# BOOST_LM5112.net
KiCad netlist of a schematic drawn in Altium Designer
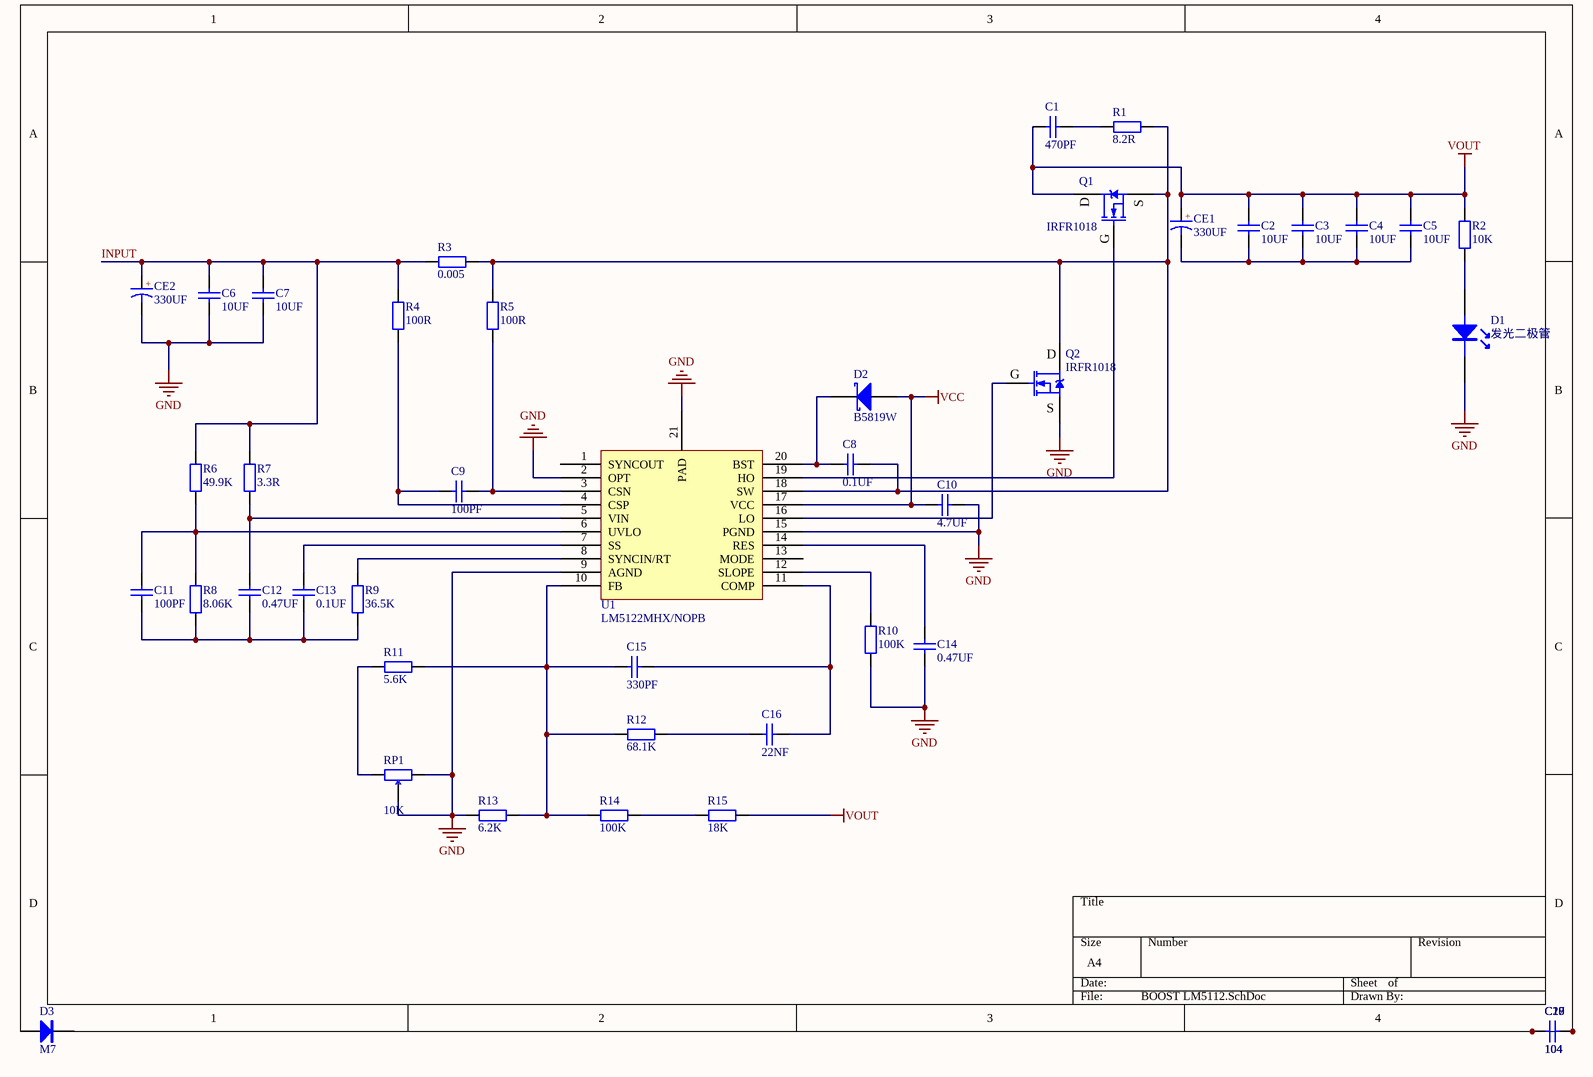
[diagram p0: BOOST LM5112.SchDoc]

(export (version "E")
  (design (tool "Eeschema 10.0.6"))
  (components
    (comp (ref "C1")
      (value "470PF")
      (footprint "C-10uF")
      (description "瓷片电容")
      (libsource (lib "0.1 - 电阻-电容-电感-磁珠-电位器") (part "CC"))
    )
    (comp (ref "C2")
      (value "10UF")
      (footprint "C-10uF")
      (description "瓷片电容")
      (libsource (lib "0.1 - 电阻-电容-电感-磁珠-电位器") (part "CC"))
    )
    (comp (ref "C3")
      (value "10UF")
      (footprint "C-10uF")
      (description "瓷片电容")
      (libsource (lib "0.1 - 电阻-电容-电感-磁珠-电位器") (part "CC"))
    )
    (comp (ref "C4")
      (value "10UF")
      (footprint "C-10uF")
      (description "瓷片电容")
      (libsource (lib "0.1 - 电阻-电容-电感-磁珠-电位器") (part "CC"))
    )
    (comp (ref "C5")
      (value "10UF")
      (footprint "C-10uF")
      (description "瓷片电容")
      (libsource (lib "0.1 - 电阻-电容-电感-磁珠-电位器") (part "CC"))
    )
    (comp (ref "C6")
      (value "10UF")
      (footprint "C-10uF")
      (description "瓷片电容")
      (libsource (lib "0.1 - 电阻-电容-电感-磁珠-电位器") (part "CC"))
    )
    (comp (ref "C7")
      (value "10UF")
      (footprint "C-10uF")
      (description "瓷片电容")
      (libsource (lib "0.1 - 电阻-电容-电感-磁珠-电位器") (part "CC"))
    )
    (comp (ref "C8")
      (value "0.1UF")
      (description "瓷片电容")
      (libsource (lib "0.1 - 电阻-电容-电感-磁珠-电位器") (part "CC"))
    )
    (comp (ref "C9")
      (value "100PF")
      (footprint "C-10uF")
      (description "瓷片电容")
      (libsource (lib "0.1 - 电阻-电容-电感-磁珠-电位器") (part "CC"))
    )
    (comp (ref "C10")
      (value "4.7UF")
      (footprint "C-10uF")
      (description "瓷片电容")
      (libsource (lib "0.1 - 电阻-电容-电感-磁珠-电位器") (part "CC"))
    )
    (comp (ref "C11")
      (value "100PF")
      (footprint "C-10uF")
      (description "瓷片电容")
      (libsource (lib "0.1 - 电阻-电容-电感-磁珠-电位器") (part "CC"))
    )
    (comp (ref "C12")
      (value "0.47UF")
      (footprint "C-10uF")
      (description "瓷片电容")
      (libsource (lib "0.1 - 电阻-电容-电感-磁珠-电位器") (part "CC"))
    )
    (comp (ref "C13")
      (value "0.1UF")
      (footprint "C-10uF")
      (description "瓷片电容")
      (libsource (lib "0.1 - 电阻-电容-电感-磁珠-电位器") (part "CC"))
    )
    (comp (ref "C14")
      (value "0.47UF")
      (footprint "C-10uF")
      (description "瓷片电容")
      (libsource (lib "0.1 - 电阻-电容-电感-磁珠-电位器") (part "CC"))
    )
    (comp (ref "C15")
      (value "330PF")
      (footprint "C-10uF")
      (description "瓷片电容")
      (libsource (lib "0.1 - 电阻-电容-电感-磁珠-电位器") (part "CC"))
    )
    (comp (ref "C16")
      (value "22NF")
      (footprint "C-10uF")
      (description "瓷片电容")
      (libsource (lib "0.1 - 电阻-电容-电感-磁珠-电位器") (part "CC"))
    )
    (comp (ref "C17")
      (value "104")
      (footprint "C-10uF")
      (description "瓷片电容")
      (libsource (lib "0.1 - 电阻-电容-电感-磁珠-电位器") (part "CC"))
    )
    (comp (ref "C18")
      (value "104")
      (footprint "C-10uF")
      (description "瓷片电容")
      (libsource (lib "0.1 - 电阻-电容-电感-磁珠-电位器") (part "CC"))
    )
    (comp (ref "C19")
      (value "104")
      (footprint "C-10uF")
      (description "瓷片电容")
      (libsource (lib "0.1 - 电阻-电容-电感-磁珠-电位器") (part "CC"))
    )
    (comp (ref "C20")
      (value "104")
      (footprint "C-10uF")
      (description "瓷片电容")
      (libsource (lib "0.1 - 电阻-电容-电感-磁珠-电位器") (part "CC"))
    )
    (comp (ref "CE1")
      (value "330UF")
      (footprint "C-10uF")
      (description "直插电解电容")
      (libsource (lib "0.1 - 电阻-电容-电感-磁珠-电位器") (part "CE"))
    )
    (comp (ref "CE2")
      (value "330UF")
      (footprint "C-10uF")
      (description "直插电解电容")
      (libsource (lib "0.1 - 电阻-电容-电感-磁珠-电位器") (part "CE"))
    )
    (comp (ref "D1")
      (value "发光二极管")
      (footprint "LED 5MM-W")
      (description "LED")
      (libsource (lib "0.2 - 二极管-TVS-ESD-整流桥") (part "发光二极管"))
    )
    (comp (ref "D2")
      (value "B5819W")
      (footprint "AXIAL-0.4")
      (description "肖特基二极管")
      (libsource (lib "0.2 - 二极管-TVS-ESD-整流桥") (part "SS14"))
    )
    (comp (ref "D3")
      (value "M7")
      (footprint "SMA")
      (description "整流二极管")
      (libsource (lib "0.2 - 二极管-TVS-ESD-整流桥") (part "M7"))
    )
    (comp (ref "Q1")
      (value "IRFR1018")
      (footprint "TO220A")
      (description "N沟道 100V/57A")
      (libsource (lib "0.4 - 三极管-场效应管-可控硅") (part "IRF3710"))
    )
    (comp (ref "Q2")
      (value "IRFR1018")
      (footprint "TO220A")
      (description "N沟道 100V/57A")
      (libsource (lib "0.4 - 三极管-场效应管-可控硅") (part "IRF3710"))
    )
    (comp (ref "R1")
      (value "8.2R")
      (footprint "AXIAL-0.4")
      (description "色环电阻")
      (libsource (lib "0.1 - 电阻-电容-电感-磁珠-电位器") (part "R-S"))
    )
    (comp (ref "R2")
      (value "10K")
      (footprint "AXIAL-0.4")
      (description "色环电阻")
      (libsource (lib "0.1 - 电阻-电容-电感-磁珠-电位器") (part "R-S"))
    )
    (comp (ref "R3")
      (value "0.005")
      (footprint "采样电阻0.005R")
      (description "色环电阻")
      (libsource (lib "0.1 - 电阻-电容-电感-磁珠-电位器") (part "R-S"))
    )
    (comp (ref "R4")
      (value "100R")
      (footprint "AXIAL-0.4")
      (description "色环电阻")
      (libsource (lib "0.1 - 电阻-电容-电感-磁珠-电位器") (part "R-S"))
    )
    (comp (ref "R5")
      (value "100R")
      (footprint "AXIAL-0.4")
      (description "色环电阻")
      (libsource (lib "0.1 - 电阻-电容-电感-磁珠-电位器") (part "R-S"))
    )
    (comp (ref "R6")
      (value "49.9K")
      (footprint "AXIAL-0.4")
      (description "色环电阻")
      (libsource (lib "0.1 - 电阻-电容-电感-磁珠-电位器") (part "R-S"))
    )
    (comp (ref "R7")
      (value "3.3R")
      (footprint "AXIAL-0.4")
      (description "色环电阻")
      (libsource (lib "0.1 - 电阻-电容-电感-磁珠-电位器") (part "R-S"))
    )
    (comp (ref "R8")
      (value "8.06K")
      (footprint "AXIAL-0.4")
      (description "色环电阻")
      (libsource (lib "0.1 - 电阻-电容-电感-磁珠-电位器") (part "R-S"))
    )
    (comp (ref "R9")
      (value "36.5K")
      (footprint "AXIAL-0.4")
      (description "色环电阻")
      (libsource (lib "0.1 - 电阻-电容-电感-磁珠-电位器") (part "R-S"))
    )
    (comp (ref "R10")
      (value "100K")
      (footprint "AXIAL-0.4")
      (description "色环电阻")
      (libsource (lib "0.1 - 电阻-电容-电感-磁珠-电位器") (part "R-S"))
    )
    (comp (ref "R11")
      (value "5.6K")
      (footprint "AXIAL-0.4")
      (description "色环电阻")
      (libsource (lib "0.1 - 电阻-电容-电感-磁珠-电位器") (part "R-S"))
    )
    (comp (ref "R12")
      (value "68.1K")
      (footprint "AXIAL-0.4")
      (description "色环电阻")
      (libsource (lib "0.1 - 电阻-电容-电感-磁珠-电位器") (part "R-S"))
    )
    (comp (ref "R13")
      (value "6.2K")
      (footprint "AXIAL-0.4")
      (description "色环电阻")
      (libsource (lib "0.1 - 电阻-电容-电感-磁珠-电位器") (part "R-S"))
    )
    (comp (ref "R14")
      (value "100K")
      (footprint "AXIAL-0.4")
      (description "色环电阻")
      (libsource (lib "0.1 - 电阻-电容-电感-磁珠-电位器") (part "R-S"))
    )
    (comp (ref "R15")
      (value "18K")
      (footprint "AXIAL-0.4")
      (description "色环电阻")
      (libsource (lib "0.1 - 电阻-电容-电感-磁珠-电位器") (part "R-S"))
    )
    (comp (ref "RP1")
      (value "10K")
      (footprint "3296W")
      (description "单联电位器")
      (libsource (lib "0.1 - 电阻-电容-电感-磁珠-电位器") (part "RP"))
    )
    (comp (ref "U1")
      (value "LM5122MHX/NOPB")
      (footprint "HTSSOP-20_L6.5-W4.4-P0.65-LS6.4-BL-EP")
      (libsource (lib "LM5122") (part "Component_1"))
    )
  )
  (nets
    (net (code "1") (name "/INPUT") (class "Default")
      (node (ref "C6") (pin "2") (pinfunction "2_2") (pintype "passive"))
      (node (ref "C7") (pin "2") (pinfunction "2_2") (pintype "passive"))
      (node (ref "CE2") (pin "1") (pinfunction "1_1") (pintype "passive"))
      (node (ref "R3") (pin "1") (pinfunction "1_1") (pintype "passive"))
      (node (ref "R4") (pin "2") (pinfunction "2_2") (pintype "passive"))
      (node (ref "R6") (pin "2") (pinfunction "2_2") (pintype "passive"))
      (node (ref "R7") (pin "2") (pinfunction "2_2") (pintype "passive"))
    )
    (net (code "2") (name "GND") (class "Default")
      (node (ref "C10") (pin "1") (pinfunction "1_1") (pintype "passive"))
      (node (ref "C14") (pin "1") (pinfunction "1_1") (pintype "passive"))
      (node (ref "C6") (pin "1") (pinfunction "1_1") (pintype "passive"))
      (node (ref "C7") (pin "1") (pinfunction "1_1") (pintype "passive"))
      (node (ref "CE2") (pin "2") (pinfunction "2_2") (pintype "passive"))
      (node (ref "D1") (pin "K") (pinfunction "2_K") (pintype "passive"))
      (node (ref "Q2") (pin "3") (pinfunction "S_3") (pintype "passive"))
      (node (ref "R10") (pin "1") (pinfunction "1_1") (pintype "passive"))
      (node (ref "R13") (pin "1") (pinfunction "1_1") (pintype "passive"))
      (node (ref "RP1") (pin "1") (pinfunction "1_1") (pintype "passive"))
      (node (ref "RP1") (pin "2") (pinfunction "2_2") (pintype "passive"))
      (node (ref "U1") (pin "15") (pinfunction "PGND_15") (pintype "passive"))
      (node (ref "U1") (pin "2") (pinfunction "OPT_2") (pintype "passive"))
      (node (ref "U1") (pin "21") (pinfunction "PAD_21") (pintype "passive"))
      (node (ref "U1") (pin "9") (pinfunction "AGND_9") (pintype "passive"))
    )
    (net (code "3") (name "Net-(C1-Pad2)") (class "Default")
      (node (ref "C1") (pin "2") (pinfunction "2_2") (pintype "passive"))
      (node (ref "R1") (pin "1") (pinfunction "1_1") (pintype "passive"))
    )
    (net (code "4") (name "Net-(C2-Pad1)") (class "Default")
      (node (ref "C2") (pin "1") (pinfunction "1_1") (pintype "passive"))
      (node (ref "C3") (pin "1") (pinfunction "1_1") (pintype "passive"))
      (node (ref "C4") (pin "1") (pinfunction "1_1") (pintype "passive"))
      (node (ref "C5") (pin "1") (pinfunction "1_1") (pintype "passive"))
      (node (ref "CE1") (pin "2") (pinfunction "2_2") (pintype "passive"))
    )
    (net (code "5") (name "Net-(C11-Pad1)") (class "Default")
      (node (ref "C11") (pin "1") (pinfunction "1_1") (pintype "passive"))
      (node (ref "C12") (pin "1") (pinfunction "1_1") (pintype "passive"))
      (node (ref "C13") (pin "1") (pinfunction "1_1") (pintype "passive"))
      (node (ref "R8") (pin "1") (pinfunction "1_1") (pintype "passive"))
      (node (ref "R9") (pin "1") (pinfunction "1_1") (pintype "passive"))
    )
    (net (code "6") (name "Net-(C16-Pad1)") (class "Default")
      (node (ref "C16") (pin "1") (pinfunction "1_1") (pintype "passive"))
      (node (ref "R12") (pin "2") (pinfunction "2_2") (pintype "passive"))
    )
    (net (code "7") (name "Net-(C17-Pad1)") (class "Default")
      (node (ref "C17") (pin "1") (pinfunction "1_1") (pintype "passive"))
      (node (ref "C18") (pin "1") (pinfunction "1_1") (pintype "passive"))
      (node (ref "C19") (pin "1") (pinfunction "1_1") (pintype "passive"))
      (node (ref "C20") (pin "1") (pinfunction "1_1") (pintype "passive"))
    )
    (net (code "8") (name "Net-(C17-Pad2)") (class "Default")
      (node (ref "C17") (pin "2") (pinfunction "2_2") (pintype "passive"))
      (node (ref "C18") (pin "2") (pinfunction "2_2") (pintype "passive"))
      (node (ref "C19") (pin "2") (pinfunction "2_2") (pintype "passive"))
      (node (ref "C20") (pin "2") (pinfunction "2_2") (pintype "passive"))
    )
    (net (code "9") (name "Net-(D1-1)") (class "Default")
      (node (ref "D1") (pin "A") (pinfunction "1_A") (pintype "passive"))
      (node (ref "R2") (pin "1") (pinfunction "1_1") (pintype "passive"))
    )
    (net (code "10") (name "Net-(D2-K)") (class "Default")
      (node (ref "C8") (pin "2") (pinfunction "2_2") (pintype "passive"))
      (node (ref "D2") (pin "2") (pinfunction "K_2") (pintype "passive"))
      (node (ref "U1") (pin "20") (pinfunction "BST_20") (pintype "passive"))
    )
    (net (code "11") (name "Net-(Q1-G)") (class "Default")
      (node (ref "Q1") (pin "1") (pinfunction "G_1") (pintype "passive"))
      (node (ref "U1") (pin "19") (pinfunction "HO_19") (pintype "passive"))
    )
    (net (code "12") (name "Net-(Q1-S)") (class "Default")
      (node (ref "C8") (pin "1") (pinfunction "1_1") (pintype "passive"))
      (node (ref "Q1") (pin "3") (pinfunction "S_3") (pintype "passive"))
      (node (ref "Q2") (pin "2") (pinfunction "D_2") (pintype "passive"))
      (node (ref "R1") (pin "2") (pinfunction "2_2") (pintype "passive"))
      (node (ref "R3") (pin "2") (pinfunction "2_2") (pintype "passive"))
      (node (ref "R5") (pin "2") (pinfunction "2_2") (pintype "passive"))
      (node (ref "U1") (pin "18") (pinfunction "SW_18") (pintype "passive"))
    )
    (net (code "13") (name "Net-(Q2-G)") (class "Default")
      (node (ref "Q2") (pin "1") (pinfunction "G_1") (pintype "passive"))
      (node (ref "U1") (pin "16") (pinfunction "LO_16") (pintype "passive"))
    )
    (net (code "14") (name "Net-(R11-Pad1)") (class "Default")
      (node (ref "R11") (pin "1") (pinfunction "1_1") (pintype "passive"))
      (node (ref "RP1") (pin "3") (pinfunction "3_3") (pintype "passive"))
    )
    (net (code "15") (name "Net-(R14-Pad2)") (class "Default")
      (node (ref "R14") (pin "2") (pinfunction "2_2") (pintype "passive"))
      (node (ref "R15") (pin "1") (pinfunction "1_1") (pintype "passive"))
    )
    (net (code "16") (name "Net-(U1-COMP)") (class "Default")
      (node (ref "C15") (pin "2") (pinfunction "2_2") (pintype "passive"))
      (node (ref "C16") (pin "2") (pinfunction "2_2") (pintype "passive"))
      (node (ref "U1") (pin "11") (pinfunction "COMP_11") (pintype "passive"))
    )
    (net (code "17") (name "Net-(U1-CSN)") (class "Default")
      (node (ref "C9") (pin "2") (pinfunction "2_2") (pintype "passive"))
      (node (ref "R5") (pin "1") (pinfunction "1_1") (pintype "passive"))
      (node (ref "U1") (pin "3") (pinfunction "CSN_3") (pintype "passive"))
    )
    (net (code "18") (name "Net-(U1-CSP)") (class "Default")
      (node (ref "C9") (pin "1") (pinfunction "1_1") (pintype "passive"))
      (node (ref "R4") (pin "1") (pinfunction "1_1") (pintype "passive"))
      (node (ref "U1") (pin "4") (pinfunction "CSP_4") (pintype "passive"))
    )
    (net (code "19") (name "Net-(U1-FB)") (class "Default")
      (node (ref "C15") (pin "1") (pinfunction "1_1") (pintype "passive"))
      (node (ref "R11") (pin "2") (pinfunction "2_2") (pintype "passive"))
      (node (ref "R12") (pin "1") (pinfunction "1_1") (pintype "passive"))
      (node (ref "R13") (pin "2") (pinfunction "2_2") (pintype "passive"))
      (node (ref "R14") (pin "1") (pinfunction "1_1") (pintype "passive"))
      (node (ref "U1") (pin "10") (pinfunction "FB_10") (pintype "passive"))
    )
    (net (code "20") (name "Net-(U1-RES)") (class "Default")
      (node (ref "C14") (pin "2") (pinfunction "2_2") (pintype "passive"))
      (node (ref "U1") (pin "14") (pinfunction "RES_14") (pintype "passive"))
    )
    (net (code "21") (name "Net-(U1-SLOPE)") (class "Default")
      (node (ref "R10") (pin "2") (pinfunction "2_2") (pintype "passive"))
      (node (ref "U1") (pin "12") (pinfunction "SLOPE_12") (pintype "passive"))
    )
    (net (code "22") (name "Net-(U1-SS)") (class "Default")
      (node (ref "C13") (pin "2") (pinfunction "2_2") (pintype "passive"))
      (node (ref "U1") (pin "7") (pinfunction "SS_7") (pintype "passive"))
    )
    (net (code "23") (name "Net-(U1-SYNCIN{slash}RT)") (class "Default")
      (node (ref "R9") (pin "2") (pinfunction "2_2") (pintype "passive"))
      (node (ref "U1") (pin "8") (pinfunction "SYNCIN/RT_8") (pintype "passive"))
    )
    (net (code "24") (name "Net-(U1-UVLO)") (class "Default")
      (node (ref "C11") (pin "2") (pinfunction "2_2") (pintype "passive"))
      (node (ref "R6") (pin "1") (pinfunction "1_1") (pintype "passive"))
      (node (ref "R8") (pin "2") (pinfunction "2_2") (pintype "passive"))
      (node (ref "U1") (pin "6") (pinfunction "UVLO_6") (pintype "passive"))
    )
    (net (code "25") (name "Net-(U1-VIN)") (class "Default")
      (node (ref "C12") (pin "2") (pinfunction "2_2") (pintype "passive"))
      (node (ref "R7") (pin "1") (pinfunction "1_1") (pintype "passive"))
      (node (ref "U1") (pin "5") (pinfunction "VIN_5") (pintype "passive"))
    )
    (net (code "26") (name "VCC") (class "Default")
      (node (ref "C10") (pin "2") (pinfunction "2_2") (pintype "passive"))
      (node (ref "D2") (pin "1") (pinfunction "A_1") (pintype "passive"))
      (node (ref "U1") (pin "17") (pinfunction "VCC_17") (pintype "passive"))
    )
    (net (code "27") (name "VOUT") (class "Default")
      (node (ref "C1") (pin "1") (pinfunction "1_1") (pintype "passive"))
      (node (ref "C2") (pin "2") (pinfunction "2_2") (pintype "passive"))
      (node (ref "C3") (pin "2") (pinfunction "2_2") (pintype "passive"))
      (node (ref "C4") (pin "2") (pinfunction "2_2") (pintype "passive"))
      (node (ref "C5") (pin "2") (pinfunction "2_2") (pintype "passive"))
      (node (ref "CE1") (pin "1") (pinfunction "1_1") (pintype "passive"))
      (node (ref "Q1") (pin "2") (pinfunction "D_2") (pintype "passive"))
      (node (ref "R15") (pin "2") (pinfunction "2_2") (pintype "passive"))
      (node (ref "R2") (pin "2") (pinfunction "2_2") (pintype "passive"))
    )
    (net (code "28") (name "unconnected-(D3-A-Pad1)") (class "Default")
      (node (ref "D3") (pin "1") (pinfunction "A_1") (pintype "passive"))
    )
    (net (code "29") (name "unconnected-(D3-K-Pad2)") (class "Default")
      (node (ref "D3") (pin "2") (pinfunction "K_2") (pintype "passive"))
    )
    (net (code "30") (name "unconnected-(U1-MODE-Pad13)") (class "Default")
      (node (ref "U1") (pin "13") (pinfunction "MODE_13") (pintype "passive"))
    )
    (net (code "31") (name "unconnected-(U1-SYNCOUT-Pad1)") (class "Default")
      (node (ref "U1") (pin "1") (pinfunction "SYNCOUT_1") (pintype "passive"))
    )
  )
)
